# POWER.net
KiCad netlist of a schematic drawn in Altium Designer
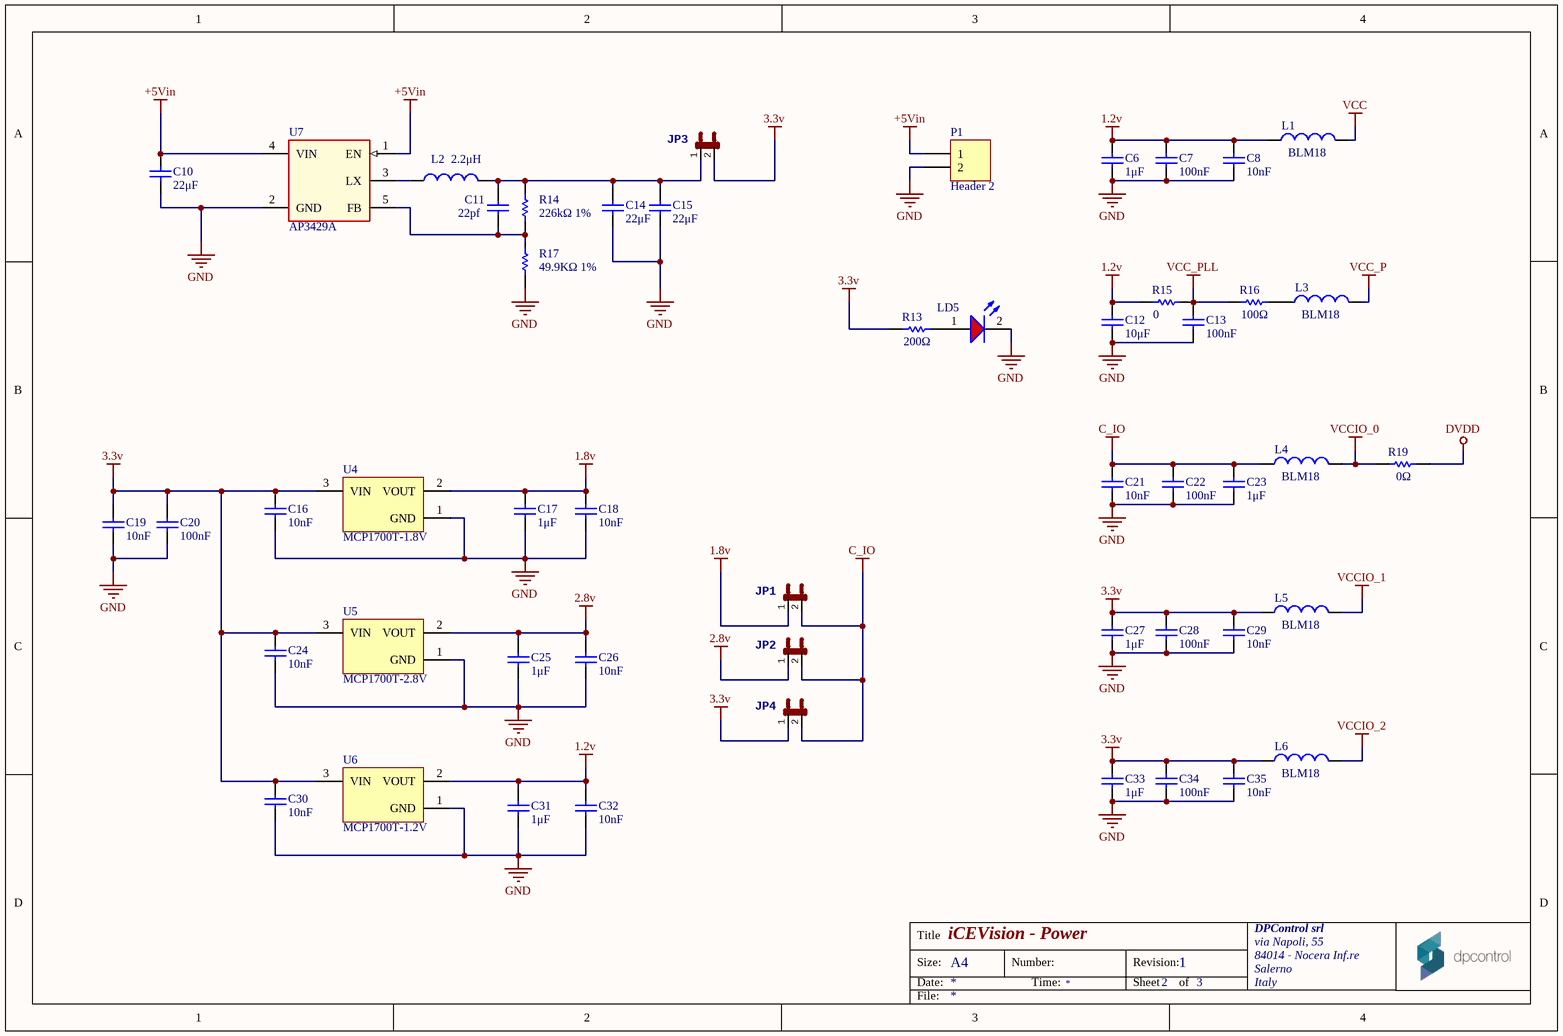
[diagram p0: POWER.SchDoc]

(export (version "E")
  (design (tool "Eeschema 10.0.6"))
  (components
    (comp (ref "C6")
      (value "1μF")
      (footprint "0603")
      (description "Ceramic Chip Capacitor - Standard")
      (fields
        (field (name "PART NO") "C0603C105K8PACTU")
        (field (name "MPN") "GPC0603105")
        (field (name "PUBLISHER") "Altium Limited")
      )
      (libsource (lib "KEMET Chip Capacitor") (part "C0603"))
    )
    (comp (ref "C7")
      (value "100nF")
      (footprint "0603")
      (description "Ceramic Chip Capacitor - Standard")
      (fields
        (field (name "PART NO") "C0603C104K8RACTU")
        (field (name "MPN") "GPC0603104")
        (field (name "PUBLISHER") "Altium Limited")
      )
      (libsource (lib "KEMET Chip Capacitor") (part "C0603"))
    )
    (comp (ref "C8")
      (value "10nF")
      (footprint "0603")
      (description "Ceramic Chip Capacitor - Standard")
      (fields
        (field (name "PART NO") "C0603C103K5RACTU")
        (field (name "MPN") "GPC0603103")
        (field (name "PUBLISHER") "Altium Limited")
      )
      (libsource (lib "KEMET Chip Capacitor") (part "C0603"))
    )
    (comp (ref "C10")
      (value "22μF")
      (footprint "0603")
      (description "Ceramic Chip Capacitor - Standard")
      (fields (field (name "MPN") "CC0603MRX5R5BB226") (field (name "MANUFACTURER") "Yageo"))
      (libsource (lib "KEMET Chip Capacitor") (part "C0603"))
    )
    (comp (ref "C11")
      (value "22pf")
      (footprint "0603")
      (description "Ceramic Chip Capacitor - Standard")
      (fields (field (name "MANUFACTURER") "Vishay") (field (name "MPN") "VJ0603A220JXACW1BC"))
      (libsource (lib "KEMET Chip Capacitor") (part "C0603"))
    )
    (comp (ref "C12")
      (value "10μF")
      (footprint "0603")
      (description "Ceramic Chip Capacitor - Standard")
      (fields
        (field (name "PART NO") "C0603C106M9PACTU")
        (field (name "MPN") "GRM219R60J106KE19D")
        (field (name "PUBLISHER") "Altium Limited")
      )
      (libsource (lib "KEMET Chip Capacitor") (part "C0603"))
    )
    (comp (ref "C13")
      (value "100nF")
      (footprint "0603")
      (description "Ceramic Chip Capacitor - Standard")
      (fields
        (field (name "PART NO") "C0603C104K8RACTU")
        (field (name "MPN") "GPC0603104")
        (field (name "PUBLISHER") "Altium Limited")
      )
      (libsource (lib "KEMET Chip Capacitor") (part "C0603"))
    )
    (comp (ref "C14")
      (value "22μF")
      (footprint "0603")
      (description "Ceramic Chip Capacitor - Standard")
      (fields (field (name "MPN") "CC0603MRX5R5BB226") (field (name "MANUFACTURER") "Yageo"))
      (libsource (lib "KEMET Chip Capacitor") (part "C0603"))
    )
    (comp (ref "C15")
      (value "22μF")
      (footprint "0603")
      (description "Ceramic Chip Capacitor - Standard")
      (fields (field (name "MPN") "CC0603MRX5R5BB226") (field (name "MANUFACTURER") "Yageo"))
      (libsource (lib "KEMET Chip Capacitor") (part "C0603"))
    )
    (comp (ref "C16")
      (value "10nF")
      (footprint "0603")
      (description "Ceramic Chip Capacitor - Standard")
      (fields
        (field (name "PART NO") "C0603C103K5RACTU")
        (field (name "MPN") "GPC0603103")
        (field (name "PUBLISHER") "Altium Limited")
      )
      (libsource (lib "KEMET Chip Capacitor") (part "C0603"))
    )
    (comp (ref "C17")
      (value "1μF")
      (footprint "0603")
      (description "Ceramic Chip Capacitor - Standard")
      (fields
        (field (name "PART NO") "C0603C105K8PACTU")
        (field (name "MPN") "GPC0603105")
        (field (name "PUBLISHER") "Altium Limited")
      )
      (libsource (lib "KEMET Chip Capacitor") (part "C0603"))
    )
    (comp (ref "C18")
      (value "10nF")
      (footprint "0603")
      (description "Ceramic Chip Capacitor - Standard")
      (fields
        (field (name "PART NO") "C0603C103K5RACTU")
        (field (name "MPN") "GPC0603103")
        (field (name "PUBLISHER") "Altium Limited")
      )
      (libsource (lib "KEMET Chip Capacitor") (part "C0603"))
    )
    (comp (ref "C19")
      (value "10nF")
      (footprint "0603")
      (description "Ceramic Chip Capacitor - Standard")
      (fields
        (field (name "PART NO") "C0603C103K5RACTU")
        (field (name "MPN") "GPC0603103")
        (field (name "PUBLISHER") "Altium Limited")
      )
      (libsource (lib "KEMET Chip Capacitor") (part "C0603"))
    )
    (comp (ref "C20")
      (value "100nF")
      (footprint "0603")
      (description "Ceramic Chip Capacitor - Standard")
      (fields
        (field (name "PART NO") "C0603C104K8RACTU")
        (field (name "MPN") "GPC0603104")
        (field (name "PUBLISHER") "Altium Limited")
      )
      (libsource (lib "KEMET Chip Capacitor") (part "C0603"))
    )
    (comp (ref "C21")
      (value "10nF")
      (footprint "0603")
      (description "Ceramic Chip Capacitor - Standard")
      (fields
        (field (name "PART NO") "C0603C103K5RACTU")
        (field (name "MPN") "GPC0603103")
        (field (name "PUBLISHER") "Altium Limited")
      )
      (libsource (lib "KEMET Chip Capacitor") (part "C0603"))
    )
    (comp (ref "C22")
      (value "100nF")
      (footprint "0603")
      (description "Ceramic Chip Capacitor - Standard")
      (fields
        (field (name "PART NO") "C0603C104K8RACTU")
        (field (name "MPN") "GPC0603104")
        (field (name "PUBLISHER") "Altium Limited")
      )
      (libsource (lib "KEMET Chip Capacitor") (part "C0603"))
    )
    (comp (ref "C23")
      (value "1μF")
      (footprint "0603")
      (description "Ceramic Chip Capacitor - Standard")
      (fields
        (field (name "PART NO") "C0603C105K8PACTU")
        (field (name "MPN") "GPC0603105")
        (field (name "PUBLISHER") "Altium Limited")
      )
      (libsource (lib "KEMET Chip Capacitor") (part "C0603"))
    )
    (comp (ref "C24")
      (value "10nF")
      (footprint "0603")
      (description "Ceramic Chip Capacitor - Standard")
      (fields
        (field (name "PART NO") "C0603C103K5RACTU")
        (field (name "MPN") "GPC0603103")
        (field (name "PUBLISHER") "Altium Limited")
      )
      (libsource (lib "KEMET Chip Capacitor") (part "C0603"))
    )
    (comp (ref "C25")
      (value "1μF")
      (footprint "0603")
      (description "Ceramic Chip Capacitor - Standard")
      (fields
        (field (name "PART NO") "C0603C105K8PACTU")
        (field (name "MPN") "GPC0603105")
        (field (name "PUBLISHER") "Altium Limited")
      )
      (libsource (lib "KEMET Chip Capacitor") (part "C0603"))
    )
    (comp (ref "C26")
      (value "10nF")
      (footprint "0603")
      (description "Ceramic Chip Capacitor - Standard")
      (fields
        (field (name "PART NO") "C0603C103K5RACTU")
        (field (name "MPN") "GPC0603103")
        (field (name "PUBLISHER") "Altium Limited")
      )
      (libsource (lib "KEMET Chip Capacitor") (part "C0603"))
    )
    (comp (ref "C27")
      (value "1μF")
      (footprint "0603")
      (description "Ceramic Chip Capacitor - Standard")
      (fields
        (field (name "PART NO") "C0603C105K8PACTU")
        (field (name "MPN") "GPC0603105")
        (field (name "PUBLISHER") "Altium Limited")
      )
      (libsource (lib "KEMET Chip Capacitor") (part "C0603"))
    )
    (comp (ref "C28")
      (value "100nF")
      (footprint "0603")
      (description "Ceramic Chip Capacitor - Standard")
      (fields
        (field (name "PART NO") "C0603C104K8RACTU")
        (field (name "MPN") "GPC0603104")
        (field (name "PUBLISHER") "Altium Limited")
      )
      (libsource (lib "KEMET Chip Capacitor") (part "C0603"))
    )
    (comp (ref "C29")
      (value "10nF")
      (footprint "0603")
      (description "Ceramic Chip Capacitor - Standard")
      (fields
        (field (name "PART NO") "C0603C103K5RACTU")
        (field (name "MPN") "GPC0603103")
        (field (name "PUBLISHER") "Altium Limited")
      )
      (libsource (lib "KEMET Chip Capacitor") (part "C0603"))
    )
    (comp (ref "C30")
      (value "10nF")
      (footprint "0603")
      (description "Ceramic Chip Capacitor - Standard")
      (fields
        (field (name "PART NO") "C0603C103K5RACTU")
        (field (name "MPN") "GPC0603103")
        (field (name "PUBLISHER") "Altium Limited")
      )
      (libsource (lib "KEMET Chip Capacitor") (part "C0603"))
    )
    (comp (ref "C31")
      (value "1μF")
      (footprint "0603")
      (description "Ceramic Chip Capacitor - Standard")
      (fields
        (field (name "PART NO") "C0603C105K8PACTU")
        (field (name "MPN") "GPC0603105")
        (field (name "PUBLISHER") "Altium Limited")
      )
      (libsource (lib "KEMET Chip Capacitor") (part "C0603"))
    )
    (comp (ref "C32")
      (value "10nF")
      (footprint "0603")
      (description "Ceramic Chip Capacitor - Standard")
      (fields
        (field (name "PART NO") "C0603C103K5RACTU")
        (field (name "MPN") "GPC0603103")
        (field (name "PUBLISHER") "Altium Limited")
      )
      (libsource (lib "KEMET Chip Capacitor") (part "C0603"))
    )
    (comp (ref "C33")
      (value "1μF")
      (footprint "0603")
      (description "Ceramic Chip Capacitor - Standard")
      (fields
        (field (name "PART NO") "C0603C105K8PACTU")
        (field (name "MPN") "GPC0603105")
        (field (name "PUBLISHER") "Altium Limited")
      )
      (libsource (lib "KEMET Chip Capacitor") (part "C0603"))
    )
    (comp (ref "C34")
      (value "100nF")
      (footprint "0603")
      (description "Ceramic Chip Capacitor - Standard")
      (fields
        (field (name "PART NO") "C0603C104K8RACTU")
        (field (name "MPN") "GPC0603104")
        (field (name "PUBLISHER") "Altium Limited")
      )
      (libsource (lib "KEMET Chip Capacitor") (part "C0603"))
    )
    (comp (ref "C35")
      (value "10nF")
      (footprint "0603")
      (description "Ceramic Chip Capacitor - Standard")
      (fields
        (field (name "PART NO") "C0603C103K5RACTU")
        (field (name "MPN") "GPC0603103")
        (field (name "PUBLISHER") "Altium Limited")
      )
      (libsource (lib "KEMET Chip Capacitor") (part "C0603"))
    )
    (comp (ref "JP1") (value "JUMPER") (footprint "JP1") (libsource (lib "jumper") (part "JP1E")))
    (comp (ref "JP2") (value "JUMPER") (footprint "JP1") (libsource (lib "jumper") (part "JP1E")))
    (comp (ref "JP3") (value "JUMPER") (footprint "JP1") (libsource (lib "jumper") (part "JP1E")))
    (comp (ref "JP4") (value "JUMPER") (footprint "JP1") (libsource (lib "jumper") (part "JP1E")))
    (comp (ref "L1")
      (value "BLM18")
      (footprint "0603")
      (description "Inductor")
      (fields (field (name "PART NO") "BLM18HE601SN1D"))
      (libsource (lib "PassiveSMT") (part "Inductor1"))
    )
    (comp (ref "L2")
      (value "2.2μH")
      (footprint "INDC2520X100")
      (description "Inductor")
      (fields (field (name "MPN") "1239AS-H-2R2M=P2"))
      (libsource (lib "PassiveSMT") (part "Inductor1"))
    )
    (comp (ref "L3")
      (value "BLM18")
      (footprint "0603")
      (description "Inductor")
      (fields (field (name "MPN") "BLM18HE601SN1D"))
      (libsource (lib "PassiveSMT") (part "Inductor1"))
    )
    (comp (ref "L4")
      (value "BLM18")
      (footprint "0603")
      (description "Inductor")
      (fields (field (name "MPN") "BLM18HE601SN1D"))
      (libsource (lib "PassiveSMT") (part "Inductor1"))
    )
    (comp (ref "L5")
      (value "BLM18")
      (footprint "0603")
      (description "Inductor")
      (fields (field (name "MPN") "BLM18HE601SN1D"))
      (libsource (lib "PassiveSMT") (part "Inductor1"))
    )
    (comp (ref "L6")
      (value "BLM18")
      (footprint "0603")
      (description "Inductor")
      (fields (field (name "MPN") "BLM18HE601SN1D"))
      (libsource (lib "PassiveSMT") (part "Inductor1"))
    )
    (comp (ref "LD5")
      (value "150060RS75000")
      (footprint "LED_0603_Red")
      (description "SMD mono-color Chip LED, WL-SMCW, Red")
      (fields
        (field (name "MANUFACTURER") "W黵th Elektronik eiSos GmbH")
        (field (name "CREATED BY") "Christin Otto")
      )
      (libsource (lib "WL-LEDsmd") (part "WL-SMCW 0603  150060RS75000"))
    )
    (comp (ref "P1")
      (value "Header 2")
      (footprint "HDR1X2")
      (description "Header, 2-Pin")
      (fields (field (name "PUBLISHER") "Altium Limited"))
      (libsource (lib "Miscellaneous Connectors") (part "Header 2"))
    )
    (comp (ref "R13")
      (value "200Ω")
      (footprint "3-0603")
      (fields
        (field (name "PART NO") "ERA3AEB201V")
        (field (name "MPN") "GPR0603200R")
        (field (name "Comment") "ERJ3EK")
        (field (name "PUBLISHER") "Altium Limited")
      )
      (libsource (lib "Panasonic Resistor") (part "ERJ3EK"))
    )
    (comp (ref "R14")
      (value "226kΩ 1%")
      (footprint "3-0603")
      (description "226k ohm 1% Tolerance, 0603 Size, 0.063 W")
      (fields (field (name "MPN") "CRCW0603226KFKEA") (field (name "MF") "Vishay"))
      (libsource (lib "Panasonic Resistor") (part "ERJ3EK"))
    )
    (comp (ref "R15")
      (value "0")
      (footprint "3-0603")
      (fields
        (field (name "PART NO") "ERJ-3GEY0R00V")
        (field (name "MPN") "CRCW06030000Z0EA")
        (field (name "Comment") "ERJ3EK")
        (field (name "PUBLISHER") "Altium Limited")
      )
      (libsource (lib "Panasonic Resistor") (part "ERJ3EK"))
    )
    (comp (ref "R16")
      (value "100Ω")
      (footprint "3-0603")
      (fields
        (field (name "PART NO") "ERA3AEB101V")
        (field (name "MPN") "GPR0603100R")
        (field (name "Comment") "ERJ3EK")
        (field (name "PUBLISHER") "Altium Limited")
      )
      (libsource (lib "Panasonic Resistor") (part "ERJ3EK"))
    )
    (comp (ref "R17")
      (value "49.9KΩ 1%")
      (footprint "3-0603")
      (fields
        (field (name "PART NO") "ERJ3EKF1002V")
        (field (name "MPN") "CRCW060349K9FKEA")
        (field (name "Comment") "ERJ3EK")
        (field (name "PUBLISHER") "Altium Limited")
      )
      (libsource (lib "iCE_Vision") (part "ERJ3EK"))
    )
    (comp (ref "R19")
      (value "0Ω")
      (footprint "3-0603")
      (fields
        (field (name "PART NO") "ERJ3GEY0R00V")
        (field (name "MPN") "CRCW06030000Z0EA")
        (field (name "Comment") "ERJ3EK")
        (field (name "PUBLISHER") "Altium Limited")
      )
      (libsource (lib "Panasonic Resistor") (part "ERJ3EK"))
    )
    (comp (ref "U4")
      (value "MCP1700T-1.8V")
      (footprint "SOT-23-TT3_N")
      (description "Low Quiescent Current LDO, 3-Pin SOT-23, Extended Temperature, Tape and Reel")
      (fields (field (name "PART NO") "MCP1700T-1802E/TT:1.8V") (field (name "MANUFACTURER") "Microchip"))
      (libsource (lib "Microchip Power Mgt Line Regulator") (part "MCP1700T-5002E/TT"))
    )
    (comp (ref "U5")
      (value "MCP1700T-2.8V")
      (footprint "SOT-23-TT3_N")
      (description "Low Quiescent Current LDO, 3-Pin SOT-23, Extended Temperature, Tape and Reel")
      (fields (field (name "PART NO") "MCP1700T-2802E/TT:2.8V") (field (name "MANUFACTURER") "Microchip"))
      (libsource (lib "Microchip Power Mgt Line Regulator") (part "MCP1700T-5002E/TT"))
    )
    (comp (ref "U6")
      (value "MCP1700T-1.2V")
      (footprint "SOT-23-TT3_N")
      (description "Low Quiescent Current LDO, 3-Pin SOT-23, Extended Temperature, Tape and Reel")
      (fields (field (name "PART NO") "MCP1700T-1202E/TT:1.2V") (field (name "MANUFACTURER") "Microchip"))
      (libsource (lib "Microchip Power Mgt Line Regulator") (part "MCP1700T-5002E/TT"))
    )
    (comp (ref "U7")
      (value "AP3429A")
      (footprint "SOT-23-5")
      (fields (field (name "MPN") "AP3429AKTTR-G1"))
      (libsource (lib "iCE_Vision") (part "AP3429A"))
    )
  )
  (nets
    (net (code "1") (name "+5Vin") (class "Default")
      (node (ref "C10") (pin "2") (pinfunction "2_2") (pintype "passive"))
      (node (ref "P1") (pin "1") (pinfunction "1_1") (pintype "passive"))
      (node (ref "U7") (pin "1") (pinfunction "EN_1") (pintype "input"))
      (node (ref "U7") (pin "4") (pinfunction "VIN_4") (pintype "power_in"))
    )
    (net (code "2") (name "1.2v") (class "Default")
      (node (ref "C12") (pin "2") (pinfunction "2_2") (pintype "passive"))
      (node (ref "C31") (pin "2") (pinfunction "2_2") (pintype "passive"))
      (node (ref "C32") (pin "2") (pinfunction "2_2") (pintype "passive"))
      (node (ref "C6") (pin "2") (pinfunction "2_2") (pintype "passive"))
      (node (ref "C7") (pin "2") (pinfunction "2_2") (pintype "passive"))
      (node (ref "C8") (pin "2") (pinfunction "2_2") (pintype "passive"))
      (node (ref "L1") (pin "1") (pinfunction "1_1") (pintype "passive"))
      (node (ref "R15") (pin "1") (pinfunction "1_1") (pintype "passive"))
      (node (ref "U6") (pin "2") (pinfunction "VOUT_2") (pintype "power_in"))
    )
    (net (code "3") (name "1.8v") (class "Default")
      (node (ref "C17") (pin "2") (pinfunction "2_2") (pintype "passive"))
      (node (ref "C18") (pin "2") (pinfunction "2_2") (pintype "passive"))
      (node (ref "JP1") (pin "1") (pinfunction "1_1") (pintype "passive"))
      (node (ref "U4") (pin "2") (pinfunction "VOUT_2") (pintype "power_in"))
    )
    (net (code "4") (name "2.8v") (class "Default")
      (node (ref "C25") (pin "2") (pinfunction "2_2") (pintype "passive"))
      (node (ref "C26") (pin "2") (pinfunction "2_2") (pintype "passive"))
      (node (ref "JP2") (pin "1") (pinfunction "1_1") (pintype "passive"))
      (node (ref "U5") (pin "2") (pinfunction "VOUT_2") (pintype "power_in"))
    )
    (net (code "5") (name "3.3v") (class "Default")
      (node (ref "C16") (pin "2") (pinfunction "2_2") (pintype "passive"))
      (node (ref "C19") (pin "2") (pinfunction "2_2") (pintype "passive"))
      (node (ref "C20") (pin "2") (pinfunction "2_2") (pintype "passive"))
      (node (ref "C24") (pin "2") (pinfunction "2_2") (pintype "passive"))
      (node (ref "C27") (pin "2") (pinfunction "2_2") (pintype "passive"))
      (node (ref "C28") (pin "2") (pinfunction "2_2") (pintype "passive"))
      (node (ref "C29") (pin "2") (pinfunction "2_2") (pintype "passive"))
      (node (ref "C30") (pin "2") (pinfunction "2_2") (pintype "passive"))
      (node (ref "C33") (pin "2") (pinfunction "2_2") (pintype "passive"))
      (node (ref "C34") (pin "2") (pinfunction "2_2") (pintype "passive"))
      (node (ref "C35") (pin "2") (pinfunction "2_2") (pintype "passive"))
      (node (ref "JP3") (pin "2") (pinfunction "2_2") (pintype "passive"))
      (node (ref "JP4") (pin "1") (pinfunction "1_1") (pintype "passive"))
      (node (ref "L5") (pin "1") (pinfunction "1_1") (pintype "passive"))
      (node (ref "L6") (pin "1") (pinfunction "1_1") (pintype "passive"))
      (node (ref "R13") (pin "1") (pinfunction "1_1") (pintype "passive"))
      (node (ref "U4") (pin "3") (pinfunction "VIN_3") (pintype "power_in"))
      (node (ref "U5") (pin "3") (pinfunction "VIN_3") (pintype "power_in"))
      (node (ref "U6") (pin "3") (pinfunction "VIN_3") (pintype "power_in"))
    )
    (net (code "6") (name "C_IO") (class "Default")
      (node (ref "C21") (pin "2") (pinfunction "2_2") (pintype "passive"))
      (node (ref "C22") (pin "2") (pinfunction "2_2") (pintype "passive"))
      (node (ref "C23") (pin "2") (pinfunction "2_2") (pintype "passive"))
      (node (ref "JP1") (pin "2") (pinfunction "2_2") (pintype "passive"))
      (node (ref "JP2") (pin "2") (pinfunction "2_2") (pintype "passive"))
      (node (ref "JP4") (pin "2") (pinfunction "2_2") (pintype "passive"))
      (node (ref "L4") (pin "1") (pinfunction "1_1") (pintype "passive"))
    )
    (net (code "7") (name "DVDD") (class "Default")
      (node (ref "R19") (pin "2") (pinfunction "2_2") (pintype "passive"))
    )
    (net (code "8") (name "GND") (class "Default")
      (node (ref "C10") (pin "1") (pinfunction "1_1") (pintype "passive"))
      (node (ref "C12") (pin "1") (pinfunction "1_1") (pintype "passive"))
      (node (ref "C13") (pin "1") (pinfunction "1_1") (pintype "passive"))
      (node (ref "C14") (pin "1") (pinfunction "1_1") (pintype "passive"))
      (node (ref "C15") (pin "1") (pinfunction "1_1") (pintype "passive"))
      (node (ref "C16") (pin "1") (pinfunction "1_1") (pintype "passive"))
      (node (ref "C17") (pin "1") (pinfunction "1_1") (pintype "passive"))
      (node (ref "C18") (pin "1") (pinfunction "1_1") (pintype "passive"))
      (node (ref "C19") (pin "1") (pinfunction "1_1") (pintype "passive"))
      (node (ref "C20") (pin "1") (pinfunction "1_1") (pintype "passive"))
      (node (ref "C21") (pin "1") (pinfunction "1_1") (pintype "passive"))
      (node (ref "C22") (pin "1") (pinfunction "1_1") (pintype "passive"))
      (node (ref "C23") (pin "1") (pinfunction "1_1") (pintype "passive"))
      (node (ref "C24") (pin "1") (pinfunction "1_1") (pintype "passive"))
      (node (ref "C25") (pin "1") (pinfunction "1_1") (pintype "passive"))
      (node (ref "C26") (pin "1") (pinfunction "1_1") (pintype "passive"))
      (node (ref "C27") (pin "1") (pinfunction "1_1") (pintype "passive"))
      (node (ref "C28") (pin "1") (pinfunction "1_1") (pintype "passive"))
      (node (ref "C29") (pin "1") (pinfunction "1_1") (pintype "passive"))
      (node (ref "C30") (pin "1") (pinfunction "1_1") (pintype "passive"))
      (node (ref "C31") (pin "1") (pinfunction "1_1") (pintype "passive"))
      (node (ref "C32") (pin "1") (pinfunction "1_1") (pintype "passive"))
      (node (ref "C33") (pin "1") (pinfunction "1_1") (pintype "passive"))
      (node (ref "C34") (pin "1") (pinfunction "1_1") (pintype "passive"))
      (node (ref "C35") (pin "1") (pinfunction "1_1") (pintype "passive"))
      (node (ref "C6") (pin "1") (pinfunction "1_1") (pintype "passive"))
      (node (ref "C7") (pin "1") (pinfunction "1_1") (pintype "passive"))
      (node (ref "C8") (pin "1") (pinfunction "1_1") (pintype "passive"))
      (node (ref "LD5") (pin "2") (pinfunction "C_2") (pintype "passive"))
      (node (ref "P1") (pin "2") (pinfunction "2_2") (pintype "passive"))
      (node (ref "R17") (pin "2") (pinfunction "2_2") (pintype "passive"))
      (node (ref "U4") (pin "1") (pinfunction "GND_1") (pintype "power_in"))
      (node (ref "U5") (pin "1") (pinfunction "GND_1") (pintype "power_in"))
      (node (ref "U6") (pin "1") (pinfunction "GND_1") (pintype "power_in"))
      (node (ref "U7") (pin "2") (pinfunction "GND_2") (pintype "power_in"))
    )
    (net (code "9") (name "Net-(C11-Pad2)") (class "Default")
      (node (ref "C11") (pin "2") (pinfunction "2_2") (pintype "passive"))
      (node (ref "C14") (pin "2") (pinfunction "2_2") (pintype "passive"))
      (node (ref "C15") (pin "2") (pinfunction "2_2") (pintype "passive"))
      (node (ref "JP3") (pin "1") (pinfunction "1_1") (pintype "passive"))
      (node (ref "L2") (pin "2") (pinfunction "2_2") (pintype "passive"))
      (node (ref "R14") (pin "2") (pinfunction "2_2") (pintype "passive"))
    )
    (net (code "10") (name "Net-(L3-Pad1)") (class "Default")
      (node (ref "L3") (pin "1") (pinfunction "1_1") (pintype "passive"))
      (node (ref "R16") (pin "2") (pinfunction "2_2") (pintype "passive"))
    )
    (net (code "11") (name "Net-(LD5-A)") (class "Default")
      (node (ref "LD5") (pin "1") (pinfunction "A_1") (pintype "passive"))
      (node (ref "R13") (pin "2") (pinfunction "2_2") (pintype "passive"))
    )
    (net (code "12") (name "Net-(U7-FB)") (class "Default")
      (node (ref "C11") (pin "1") (pinfunction "1_1") (pintype "passive"))
      (node (ref "R14") (pin "1") (pinfunction "1_1") (pintype "passive"))
      (node (ref "R17") (pin "1") (pinfunction "1_1") (pintype "passive"))
      (node (ref "U7") (pin "5") (pinfunction "FB_5") (pintype "passive"))
    )
    (net (code "13") (name "Net-(U7-LX)") (class "Default")
      (node (ref "L2") (pin "1") (pinfunction "1_1") (pintype "passive"))
      (node (ref "U7") (pin "3") (pinfunction "LX_3") (pintype "power_in"))
    )
    (net (code "14") (name "VCC") (class "Default")
      (node (ref "L1") (pin "2") (pinfunction "2_2") (pintype "passive"))
    )
    (net (code "15") (name "VCCIO_0") (class "Default")
      (node (ref "L4") (pin "2") (pinfunction "2_2") (pintype "passive"))
      (node (ref "R19") (pin "1") (pinfunction "1_1") (pintype "passive"))
    )
    (net (code "16") (name "VCCIO_1") (class "Default")
      (node (ref "L5") (pin "2") (pinfunction "2_2") (pintype "passive"))
    )
    (net (code "17") (name "VCCIO_2") (class "Default")
      (node (ref "L6") (pin "2") (pinfunction "2_2") (pintype "passive"))
    )
    (net (code "18") (name "VCC_P") (class "Default")
      (node (ref "L3") (pin "2") (pinfunction "2_2") (pintype "passive"))
    )
    (net (code "19") (name "VCC_PLL") (class "Default")
      (node (ref "C13") (pin "2") (pinfunction "2_2") (pintype "passive"))
      (node (ref "R15") (pin "2") (pinfunction "2_2") (pintype "passive"))
      (node (ref "R16") (pin "1") (pinfunction "1_1") (pintype "passive"))
    )
  )
)
